# BMS_Microcontroller.net
KiCad netlist of a schematic drawn in Altium Designer
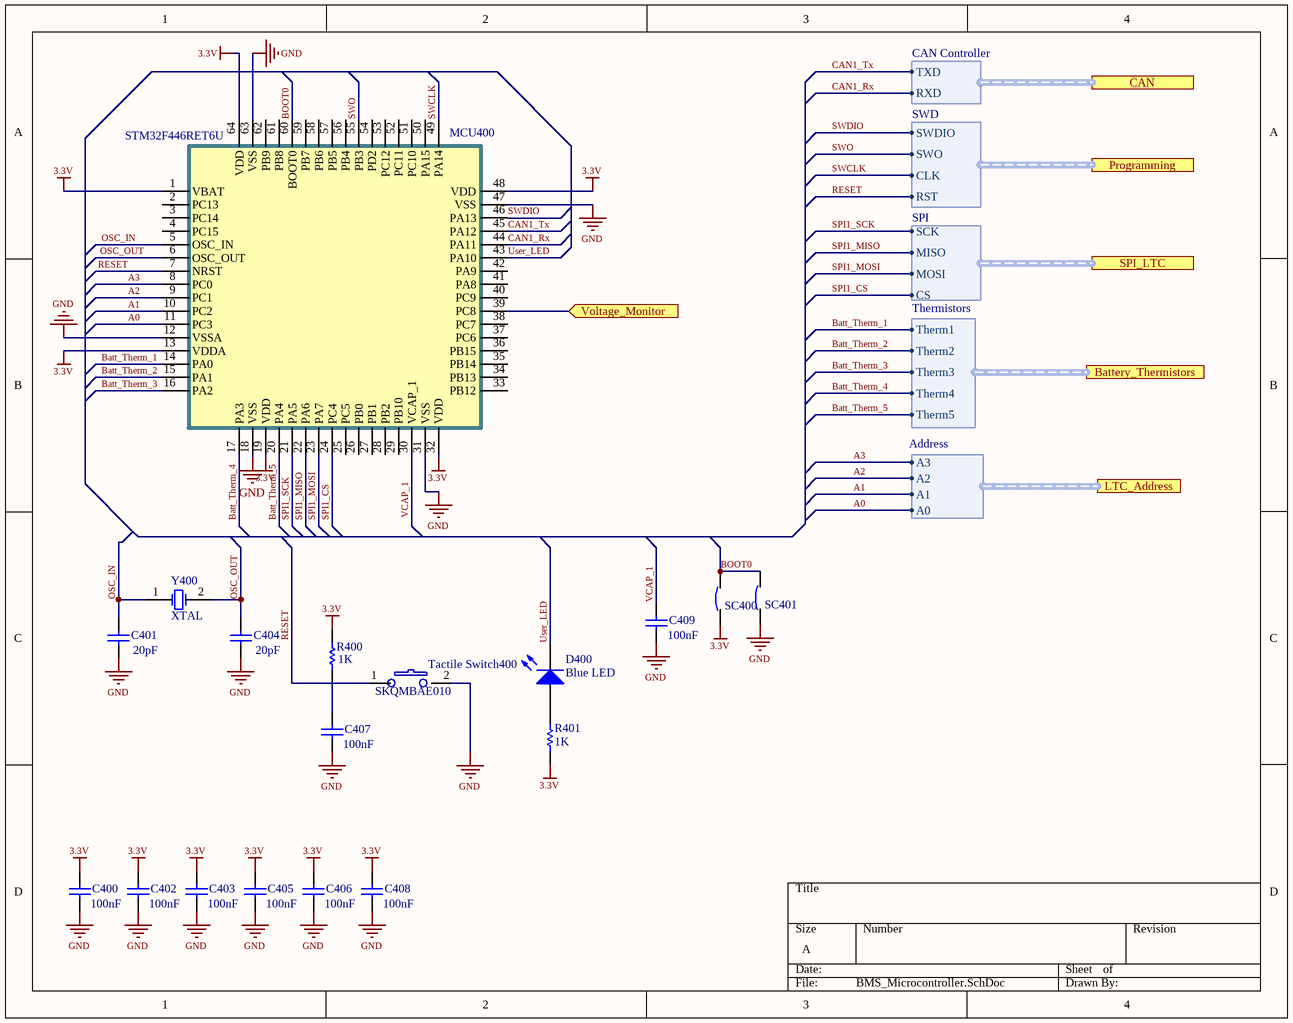
[diagram p0: BMS_Microcontroller.SchDoc]

(export (version "E")
  (design (tool "Eeschema 10.0.6"))
  (components
    (comp (ref "C400")
      (value "100nF")
      (footprint "CAPC2012X14N")
      (description "Capacitor")
      (fields (field (name "Comment") "Cap") (field (name "PUBLISHER") "Altium Limited"))
      (libsource (lib "Miscellaneous Devices") (part "Cap"))
    )
    (comp (ref "C401")
      (value "20pF")
      (footprint "CAPC2012X14N")
      (description "Capacitor")
      (fields (field (name "Comment") "Cap") (field (name "PUBLISHER") "Altium Limited"))
      (libsource (lib "Miscellaneous Devices") (part "Cap"))
    )
    (comp (ref "C402")
      (value "100nF")
      (footprint "CAPC2012X14N")
      (description "Capacitor")
      (fields (field (name "Comment") "Cap") (field (name "PUBLISHER") "Altium Limited"))
      (libsource (lib "Miscellaneous Devices") (part "Cap"))
    )
    (comp (ref "C403")
      (value "100nF")
      (footprint "CAPC2012X14N")
      (description "Capacitor")
      (fields (field (name "Comment") "Cap") (field (name "PUBLISHER") "Altium Limited"))
      (libsource (lib "Miscellaneous Devices") (part "Cap"))
    )
    (comp (ref "C404")
      (value "20pF")
      (footprint "CAPC2012X14N")
      (description "Capacitor")
      (fields (field (name "Comment") "Cap") (field (name "PUBLISHER") "Altium Limited"))
      (libsource (lib "Miscellaneous Devices") (part "Cap"))
    )
    (comp (ref "C405")
      (value "100nF")
      (footprint "CAPC2012X14N")
      (description "Capacitor")
      (fields (field (name "Comment") "Cap") (field (name "PUBLISHER") "Altium Limited"))
      (libsource (lib "Miscellaneous Devices") (part "Cap"))
    )
    (comp (ref "C406")
      (value "100nF")
      (footprint "CAPC2012X14N")
      (description "Capacitor")
      (fields (field (name "Comment") "Cap") (field (name "PUBLISHER") "Altium Limited"))
      (libsource (lib "Miscellaneous Devices") (part "Cap"))
    )
    (comp (ref "C407")
      (value "100nF")
      (footprint "CAPC2012X14N")
      (description "Capacitor")
      (fields (field (name "Comment") "Cap") (field (name "PUBLISHER") "Altium Limited"))
      (libsource (lib "Miscellaneous Devices") (part "Cap"))
    )
    (comp (ref "C408")
      (value "100nF")
      (footprint "CAPC2012X14N")
      (description "Capacitor")
      (fields (field (name "Comment") "Cap") (field (name "PUBLISHER") "Altium Limited"))
      (libsource (lib "Miscellaneous Devices") (part "Cap"))
    )
    (comp (ref "C409")
      (value "100nF")
      (footprint "CAPC2012X14N")
      (description "Capacitor")
      (fields (field (name "Comment") "Cap") (field (name "PUBLISHER") "Altium Limited"))
      (libsource (lib "Miscellaneous Devices") (part "Cap"))
    )
    (comp (ref "D400")
      (value "Blue LED")
      (footprint "SMD Blue LED")
      (description "Typical INFRARED GaAs LED")
      (fields (field (name "PUBLISHER") "Altium Limited"))
      (libsource (lib "Miscellaneous Devices") (part "LED0"))
    )
    (comp (ref "MCU400")
      (value "STM32F446RET6U")
      (footprint "LQFP50P1200X1200X160-64N")
      (libsource (lib "STM32F446RET6U") (part "STM32F446RET6U"))
    )
    (comp (ref "R400")
      (value "1K")
      (footprint "RESC2012X07N")
      (description "Resistor")
      (fields (field (name "Comment") "Res1") (field (name "PUBLISHER") "Altium Limited"))
      (libsource (lib "Miscellaneous Devices") (part "Res1"))
    )
    (comp (ref "R401")
      (value "1K")
      (footprint "RESC2012X07N")
      (description "Resistor")
      (fields (field (name "Comment") "Res1") (field (name "PUBLISHER") "Altium Limited"))
      (libsource (lib "Miscellaneous Devices") (part "Res1"))
    )
    (comp (ref "SC400")
      (value "Short Circuit")
      (footprint "RESC2012X07N")
      (libsource (lib "ShortCircuit") (part "Short Circuit"))
    )
    (comp (ref "SC401")
      (value "Short Circuit")
      (footprint "RESC2012X07N")
      (libsource (lib "ShortCircuit") (part "Short Circuit"))
    )
    (comp (ref "Tactile Switch400")
      (value "SKQMBAE010")
      (footprint "SKTHBAE010")
      (description "ALPS 6.0x3.5x4.3mm SMD Tactile Switch, Ratings 50mA/12VDC")
      (libsource (lib "TactileSwitch_SKQMBAE010") (part "SKQMBAE010"))
    )
    (comp (ref "Y400")
      (value "XTAL")
      (footprint "FOXSDLF/080-20")
      (description "Crystal Oscillator")
      (fields (field (name "PUBLISHER") "Altium Limited"))
      (libsource (lib "Miscellaneous Devices") (part "XTAL"))
    )
  )
  (nets
    (net (code "7") (name "/BOOT0") (class "Default")
      (node (ref "MCU400") (pin "60") (pinfunction "BOOT0_60") (pintype "passive"))
      (node (ref "SC400") (pin "2") (pinfunction "2_2") (pintype "passive"))
      (node (ref "SC401") (pin "2") (pinfunction "2_2") (pintype "passive"))
    )
    (net (code "8") (name "/Batt_Therm_1") (class "Default")
      (node (ref "MCU400") (pin "14") (pinfunction "PA0_14") (pintype "passive"))
    )
    (net (code "9") (name "/Batt_Therm_2") (class "Default")
      (node (ref "MCU400") (pin "15") (pinfunction "PA1_15") (pintype "passive"))
    )
    (net (code "10") (name "/Batt_Therm_3") (class "Default")
      (node (ref "MCU400") (pin "16") (pinfunction "PA2_16") (pintype "passive"))
    )
    (net (code "11") (name "/Batt_Therm_4") (class "Default")
      (node (ref "MCU400") (pin "17") (pinfunction "PA3_17") (pintype "passive"))
    )
    (net (code "12") (name "/Batt_Therm_5") (class "Default")
      (node (ref "MCU400") (pin "20") (pinfunction "PA4_20") (pintype "passive"))
    )
    (net (code "13") (name "/CAN1_Rx") (class "Default")
      (node (ref "MCU400") (pin "44") (pinfunction "PA11_44") (pintype "passive"))
    )
    (net (code "14") (name "/CAN1_Tx") (class "Default")
      (node (ref "MCU400") (pin "45") (pinfunction "PA12_45") (pintype "passive"))
    )
    (net (code "15") (name "/OSC_IN") (class "Default")
      (node (ref "C401") (pin "1") (pinfunction "1_1") (pintype "passive"))
      (node (ref "MCU400") (pin "5") (pinfunction "OSC_IN_5") (pintype "passive"))
      (node (ref "Y400") (pin "1") (pinfunction "OSC1_1") (pintype "passive"))
    )
    (net (code "16") (name "/OSC_OUT") (class "Default")
      (node (ref "C404") (pin "1") (pinfunction "1_1") (pintype "passive"))
      (node (ref "MCU400") (pin "6") (pinfunction "OSC_OUT_6") (pintype "passive"))
      (node (ref "Y400") (pin "2") (pinfunction "OSC2_2") (pintype "passive"))
    )
    (net (code "17") (name "/RESET") (class "Default")
      (node (ref "C407") (pin "1") (pinfunction "1_1") (pintype "passive"))
      (node (ref "MCU400") (pin "7") (pinfunction "NRST_7") (pintype "passive"))
      (node (ref "R400") (pin "1") (pinfunction "1_1") (pintype "passive"))
      (node (ref "Tactile Switch400") (pin "1") (pinfunction "1_1") (pintype "passive"))
    )
    (net (code "18") (name "/SPI1_CS") (class "Default")
      (node (ref "MCU400") (pin "24") (pinfunction "PC4_24") (pintype "passive"))
    )
    (net (code "19") (name "/SPI1_MISO") (class "Default")
      (node (ref "MCU400") (pin "22") (pinfunction "PA6_22") (pintype "passive"))
    )
    (net (code "20") (name "/SPI1_MOSI") (class "Default")
      (node (ref "MCU400") (pin "23") (pinfunction "PA7_23") (pintype "passive"))
    )
    (net (code "21") (name "/SPI1_SCK") (class "Default")
      (node (ref "MCU400") (pin "21") (pinfunction "PA5_21") (pintype "passive"))
    )
    (net (code "22") (name "/SWCLK") (class "Default")
      (node (ref "MCU400") (pin "49") (pinfunction "PA14_49") (pintype "passive"))
    )
    (net (code "23") (name "/SWDIO") (class "Default")
      (node (ref "MCU400") (pin "46") (pinfunction "PA13_46") (pintype "passive"))
    )
    (net (code "24") (name "/SWO") (class "Default")
      (node (ref "MCU400") (pin "55") (pinfunction "PB3_55") (pintype "passive"))
    )
    (net (code "25") (name "/User_LED") (class "Default")
      (node (ref "D400") (pin "2") (pinfunction "K_2") (pintype "passive"))
      (node (ref "MCU400") (pin "43") (pinfunction "PA10_43") (pintype "passive"))
    )
    (net (code "26") (name "/VCAP_1") (class "Default")
      (node (ref "C409") (pin "1") (pinfunction "1_1") (pintype "passive"))
      (node (ref "MCU400") (pin "30") (pinfunction "VCAP_1_30") (pintype "passive"))
    )
    (net (code "27") (name "/Voltage_Monitor") (class "Default")
      (node (ref "MCU400") (pin "39") (pinfunction "PC8_39") (pintype "passive"))
    )
    (net (code "33") (name "/Α0") (class "Default")
      (node (ref "MCU400") (pin "11") (pinfunction "PC3_11") (pintype "passive"))
    )
    (net (code "34") (name "/Α1") (class "Default")
      (node (ref "MCU400") (pin "10") (pinfunction "PC2_10") (pintype "passive"))
    )
    (net (code "35") (name "/Α2") (class "Default")
      (node (ref "MCU400") (pin "9") (pinfunction "PC1_9") (pintype "passive"))
    )
    (net (code "36") (name "/Α3") (class "Default")
      (node (ref "MCU400") (pin "8") (pinfunction "PC0_8") (pintype "passive"))
    )
    (net (code "37") (name "3.3V") (class "Default")
      (node (ref "C400") (pin "1") (pinfunction "1_1") (pintype "passive"))
      (node (ref "C402") (pin "1") (pinfunction "1_1") (pintype "passive"))
      (node (ref "C403") (pin "1") (pinfunction "1_1") (pintype "passive"))
      (node (ref "C405") (pin "1") (pinfunction "1_1") (pintype "passive"))
      (node (ref "C406") (pin "1") (pinfunction "1_1") (pintype "passive"))
      (node (ref "C408") (pin "1") (pinfunction "1_1") (pintype "passive"))
      (node (ref "MCU400") (pin "1") (pinfunction "VBAT_1") (pintype "passive"))
      (node (ref "MCU400") (pin "13") (pinfunction "VDDA_13") (pintype "passive"))
      (node (ref "MCU400") (pin "19") (pinfunction "VDD_19") (pintype "passive"))
      (node (ref "MCU400") (pin "32") (pinfunction "VDD_32") (pintype "passive"))
      (node (ref "MCU400") (pin "48") (pinfunction "VDD_48") (pintype "passive"))
      (node (ref "MCU400") (pin "64") (pinfunction "VDD_64") (pintype "passive"))
      (node (ref "R400") (pin "2") (pinfunction "2_2") (pintype "passive"))
      (node (ref "R401") (pin "2") (pinfunction "2_2") (pintype "passive"))
      (node (ref "SC400") (pin "1") (pinfunction "1_1") (pintype "passive"))
    )
    (net (code "38") (name "GND") (class "Default")
      (node (ref "C400") (pin "2") (pinfunction "2_2") (pintype "passive"))
      (node (ref "C401") (pin "2") (pinfunction "2_2") (pintype "passive"))
      (node (ref "C402") (pin "2") (pinfunction "2_2") (pintype "passive"))
      (node (ref "C403") (pin "2") (pinfunction "2_2") (pintype "passive"))
      (node (ref "C404") (pin "2") (pinfunction "2_2") (pintype "passive"))
      (node (ref "C405") (pin "2") (pinfunction "2_2") (pintype "passive"))
      (node (ref "C406") (pin "2") (pinfunction "2_2") (pintype "passive"))
      (node (ref "C407") (pin "2") (pinfunction "2_2") (pintype "passive"))
      (node (ref "C408") (pin "2") (pinfunction "2_2") (pintype "passive"))
      (node (ref "C409") (pin "2") (pinfunction "2_2") (pintype "passive"))
      (node (ref "MCU400") (pin "12") (pinfunction "VSSA_12") (pintype "passive"))
      (node (ref "MCU400") (pin "18") (pinfunction "VSS_18") (pintype "passive"))
      (node (ref "MCU400") (pin "31") (pinfunction "VSS_31") (pintype "passive"))
      (node (ref "MCU400") (pin "47") (pinfunction "VSS_47") (pintype "passive"))
      (node (ref "MCU400") (pin "63") (pinfunction "VSS_63") (pintype "passive"))
      (node (ref "SC401") (pin "1") (pinfunction "1_1") (pintype "passive"))
      (node (ref "Tactile Switch400") (pin "2") (pinfunction "2_2") (pintype "passive"))
    )
    (net (code "39") (name "Net-(D400-A)") (class "Default")
      (node (ref "D400") (pin "1") (pinfunction "A_1") (pintype "passive"))
      (node (ref "R401") (pin "1") (pinfunction "1_1") (pintype "passive"))
    )
    (net (code "40") (name "unconnected-(MCU400-PA8-Pad41)") (class "Default")
      (node (ref "MCU400") (pin "41") (pinfunction "PA8_41") (pintype "passive"))
    )
    (net (code "41") (name "unconnected-(MCU400-PA9-Pad42)") (class "Default")
      (node (ref "MCU400") (pin "42") (pinfunction "PA9_42") (pintype "passive"))
    )
    (net (code "42") (name "unconnected-(MCU400-PA15-Pad50)") (class "Default")
      (node (ref "MCU400") (pin "50") (pinfunction "PA15_50") (pintype "passive"))
    )
    (net (code "43") (name "unconnected-(MCU400-PB0-Pad26)") (class "Default")
      (node (ref "MCU400") (pin "26") (pinfunction "PB0_26") (pintype "passive"))
    )
    (net (code "44") (name "unconnected-(MCU400-PB1-Pad27)") (class "Default")
      (node (ref "MCU400") (pin "27") (pinfunction "PB1_27") (pintype "passive"))
    )
    (net (code "45") (name "unconnected-(MCU400-PB2-Pad28)") (class "Default")
      (node (ref "MCU400") (pin "28") (pinfunction "PB2_28") (pintype "passive"))
    )
    (net (code "46") (name "unconnected-(MCU400-PB4-Pad56)") (class "Default")
      (node (ref "MCU400") (pin "56") (pinfunction "PB4_56") (pintype "passive"))
    )
    (net (code "47") (name "unconnected-(MCU400-PB5-Pad57)") (class "Default")
      (node (ref "MCU400") (pin "57") (pinfunction "PB5_57") (pintype "passive"))
    )
    (net (code "48") (name "unconnected-(MCU400-PB6-Pad58)") (class "Default")
      (node (ref "MCU400") (pin "58") (pinfunction "PB6_58") (pintype "passive"))
    )
    (net (code "49") (name "unconnected-(MCU400-PB7-Pad59)") (class "Default")
      (node (ref "MCU400") (pin "59") (pinfunction "PB7_59") (pintype "passive"))
    )
    (net (code "50") (name "unconnected-(MCU400-PB8-Pad61)") (class "Default")
      (node (ref "MCU400") (pin "61") (pinfunction "PB8_61") (pintype "passive"))
    )
    (net (code "51") (name "unconnected-(MCU400-PB9-Pad62)") (class "Default")
      (node (ref "MCU400") (pin "62") (pinfunction "PB9_62") (pintype "passive"))
    )
    (net (code "52") (name "unconnected-(MCU400-PB10-Pad29)") (class "Default")
      (node (ref "MCU400") (pin "29") (pinfunction "PB10_29") (pintype "passive"))
    )
    (net (code "53") (name "unconnected-(MCU400-PB12-Pad33)") (class "Default")
      (node (ref "MCU400") (pin "33") (pinfunction "PB12_33") (pintype "passive"))
    )
    (net (code "54") (name "unconnected-(MCU400-PB13-Pad34)") (class "Default")
      (node (ref "MCU400") (pin "34") (pinfunction "PB13_34") (pintype "passive"))
    )
    (net (code "55") (name "unconnected-(MCU400-PB14-Pad35)") (class "Default")
      (node (ref "MCU400") (pin "35") (pinfunction "PB14_35") (pintype "passive"))
    )
    (net (code "56") (name "unconnected-(MCU400-PB15-Pad36)") (class "Default")
      (node (ref "MCU400") (pin "36") (pinfunction "PB15_36") (pintype "passive"))
    )
    (net (code "57") (name "unconnected-(MCU400-PC5-Pad25)") (class "Default")
      (node (ref "MCU400") (pin "25") (pinfunction "PC5_25") (pintype "passive"))
    )
    (net (code "58") (name "unconnected-(MCU400-PC6-Pad37)") (class "Default")
      (node (ref "MCU400") (pin "37") (pinfunction "PC6_37") (pintype "passive"))
    )
    (net (code "59") (name "unconnected-(MCU400-PC7-Pad38)") (class "Default")
      (node (ref "MCU400") (pin "38") (pinfunction "PC7_38") (pintype "passive"))
    )
    (net (code "60") (name "unconnected-(MCU400-PC9-Pad40)") (class "Default")
      (node (ref "MCU400") (pin "40") (pinfunction "PC9_40") (pintype "passive"))
    )
    (net (code "61") (name "unconnected-(MCU400-PC10-Pad51)") (class "Default")
      (node (ref "MCU400") (pin "51") (pinfunction "PC10_51") (pintype "passive"))
    )
    (net (code "62") (name "unconnected-(MCU400-PC11-Pad52)") (class "Default")
      (node (ref "MCU400") (pin "52") (pinfunction "PC11_52") (pintype "passive"))
    )
    (net (code "63") (name "unconnected-(MCU400-PC12-Pad53)") (class "Default")
      (node (ref "MCU400") (pin "53") (pinfunction "PC12_53") (pintype "passive"))
    )
    (net (code "64") (name "unconnected-(MCU400-PC13-Pad2)") (class "Default")
      (node (ref "MCU400") (pin "2") (pinfunction "PC13_2") (pintype "passive"))
    )
    (net (code "65") (name "unconnected-(MCU400-PC14-Pad3)") (class "Default")
      (node (ref "MCU400") (pin "3") (pinfunction "PC14_3") (pintype "passive"))
    )
    (net (code "66") (name "unconnected-(MCU400-PC15-Pad4)") (class "Default")
      (node (ref "MCU400") (pin "4") (pinfunction "PC15_4") (pintype "passive"))
    )
    (net (code "67") (name "unconnected-(MCU400-PD2-Pad54)") (class "Default")
      (node (ref "MCU400") (pin "54") (pinfunction "PD2_54") (pintype "passive"))
    )
  )
)
